# POWER_SUPPLY.net
KiCad netlist of a schematic drawn in Altium Designer
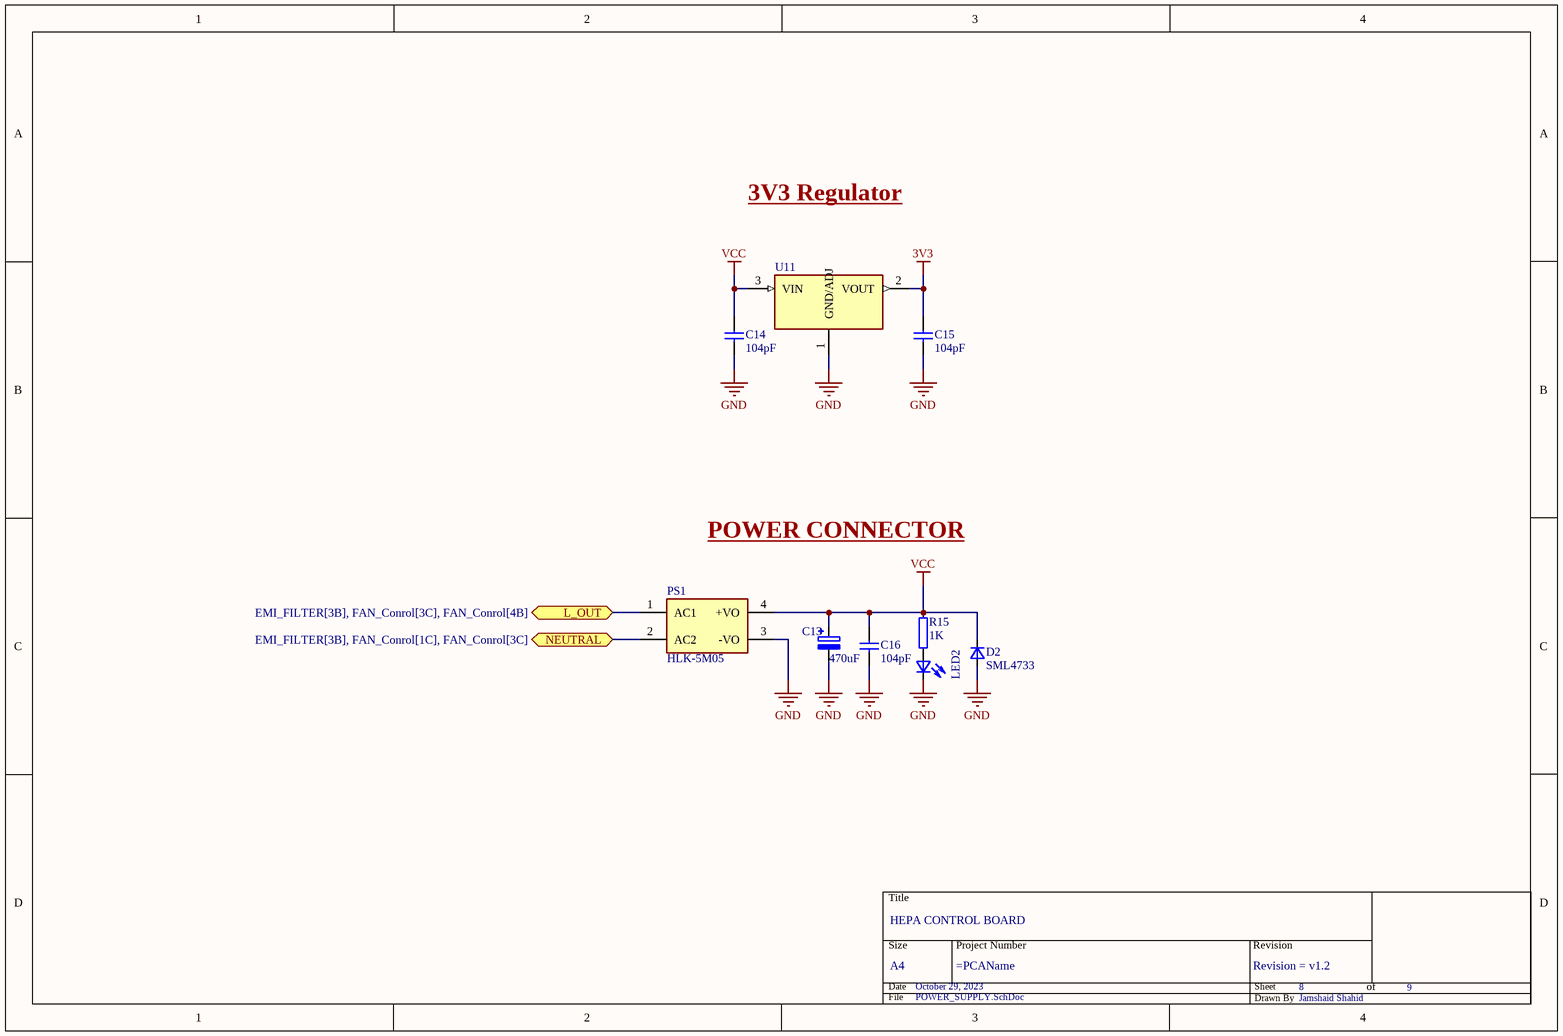
[diagram p0: POWER_SUPPLY.SchDoc]

(export (version "E")
  (design (tool "Eeschema 10.0.6"))
  (components
    (comp (ref "C13")
      (value "470uF")
      (footprint "CAPPRD500W60D1000H1300")
      (description "Aluminum Electrolytic Capacitors - Radial Leaded")
      (fields (field (name "PART NUMBER") "Cap Electrolytic") (field (name "PUBLISHER") "Metal Circuits"))
      (libsource (lib "HEPA_LIB") (part "Electrolytic Capacitor"))
    )
    (comp (ref "C14")
      (value "104pF")
      (footprint "CAPC2012X140N")
      (fields (field (name "PART NUMBER") "CAP_0805") (field (name "PUBLISHER") "Metal Circuits"))
      (libsource (lib "HEPA_LIB") (part "CAP_0805"))
    )
    (comp (ref "C15")
      (value "104pF")
      (footprint "CAPC2012X140N")
      (fields (field (name "PART NUMBER") "CAP_0805") (field (name "PUBLISHER") "Metal Circuits"))
      (libsource (lib "HEPA_LIB") (part "CAP_0805"))
    )
    (comp (ref "C16")
      (value "104pF")
      (footprint "CAPC2012X140N")
      (fields (field (name "PART NUMBER") "CAP_0805") (field (name "PUBLISHER") "Metal Circuits"))
      (libsource (lib "HEPA_LIB") (part "CAP_0805"))
    )
    (comp (ref "D2")
      (value "SML4733")
      (footprint "DO-214AC")
      (description "Zener Diode Single 5.1V 10% 7Ohm 1000mW 2-Pin SMA")
      (fields (field (name "PUBLISHER") "Metal Circuits"))
      (libsource (lib "HEPA_LIB") (part "SML4733"))
    )
    (comp (ref "LED2")
      (value "LED_0603")
      (footprint "LED_KP-2012")
      (description "LED SMD 0603")
      (fields (field (name "PUBLISHER") "Metal Circuits"))
      (libsource (lib "HEPA_LIB") (part "LED_0603"))
    )
    (comp (ref "PS1")
      (value "HLK-5M05")
      (footprint "CONV_HLK-5M05")
      (description "5V 1A 90VAC~265VAC 120V~350V 5W AC-DC 69% Plugin Power Modules ROHS")
      (fields (field (name "MANUFACTURER") "HI-LINK") (field (name "PUBLISHER") "Metal Circuits"))
      (libsource (lib "HEPA_LIB") (part "HLK-5M05"))
    )
    (comp (ref "R15")
      (value "1K")
      (footprint "RESC2012X65N")
      (description "RES SMD 1% 1/10W 0805")
      (fields (field (name "PART NUMBER") "RES_0805") (field (name "PUBLISHER") "Metal Circuits"))
      (libsource (lib "HEPA_LIB") (part "RES_0805"))
    )
    (comp (ref "U11")
      (value "AMS1117-3.3")
      (footprint "SOT229P700X180-4N")
      (description "Sot223/Pkg 1-Amp 3.3-Volt Low Drop Out Voltage Regulatator")
      (fields (field (name "MANUFACTURER") "AMS") (field (name "PUBLISHER") "Metal Circuits"))
      (libsource (lib "HEPA_LIB") (part "AMS1117-3.3"))
    )
  )
  (nets
    (net (code "1") (name "/L_OUT") (class "Default")
      (node (ref "PS1") (pin "1") (pinfunction "AC1_1") (pintype "passive"))
    )
    (net (code "2") (name "/NEUTRAL") (class "Default")
      (node (ref "PS1") (pin "2") (pinfunction "AC2_2") (pintype "passive"))
    )
    (net (code "3") (name "3V3") (class "Default")
      (node (ref "C15") (pin "2") (pinfunction "2_2") (pintype "passive"))
      (node (ref "U11") (pin "2") (pinfunction "VOUT_2") (pintype "output"))
    )
    (net (code "4") (name "GND") (class "Default")
      (node (ref "C13") (pin "2") (pinfunction "2_2") (pintype "passive"))
      (node (ref "C14") (pin "1") (pinfunction "1_1") (pintype "passive"))
      (node (ref "C15") (pin "1") (pinfunction "1_1") (pintype "passive"))
      (node (ref "C16") (pin "1") (pinfunction "1_1") (pintype "passive"))
      (node (ref "D2") (pin "1") (pinfunction "ANNODE_1") (pintype "passive"))
      (node (ref "LED2") (pin "2") (pinfunction "Cathode_2") (pintype "passive"))
      (node (ref "PS1") (pin "3") (pinfunction "-VO_3") (pintype "passive"))
      (node (ref "U11") (pin "1") (pinfunction "GND/ADJ_1") (pintype "power_in"))
    )
    (net (code "5") (name "Net-(LED2-Anode)") (class "Default")
      (node (ref "LED2") (pin "1") (pinfunction "Anode_1") (pintype "passive"))
      (node (ref "R15") (pin "1") (pinfunction "1_1") (pintype "passive"))
    )
    (net (code "6") (name "VCC") (class "Default")
      (node (ref "C13") (pin "1") (pinfunction "1_1") (pintype "passive"))
      (node (ref "C14") (pin "2") (pinfunction "2_2") (pintype "passive"))
      (node (ref "C16") (pin "2") (pinfunction "2_2") (pintype "passive"))
      (node (ref "D2") (pin "2") (pinfunction "CATHODE_2") (pintype "passive"))
      (node (ref "PS1") (pin "4") (pinfunction "+VO_4") (pintype "passive"))
      (node (ref "R15") (pin "2") (pinfunction "2_2") (pintype "passive"))
      (node (ref "U11") (pin "3") (pinfunction "VIN_3") (pintype "input"))
    )
  )
)
